# Sheet3.net
KiCad netlist of a schematic drawn in Altium Designer
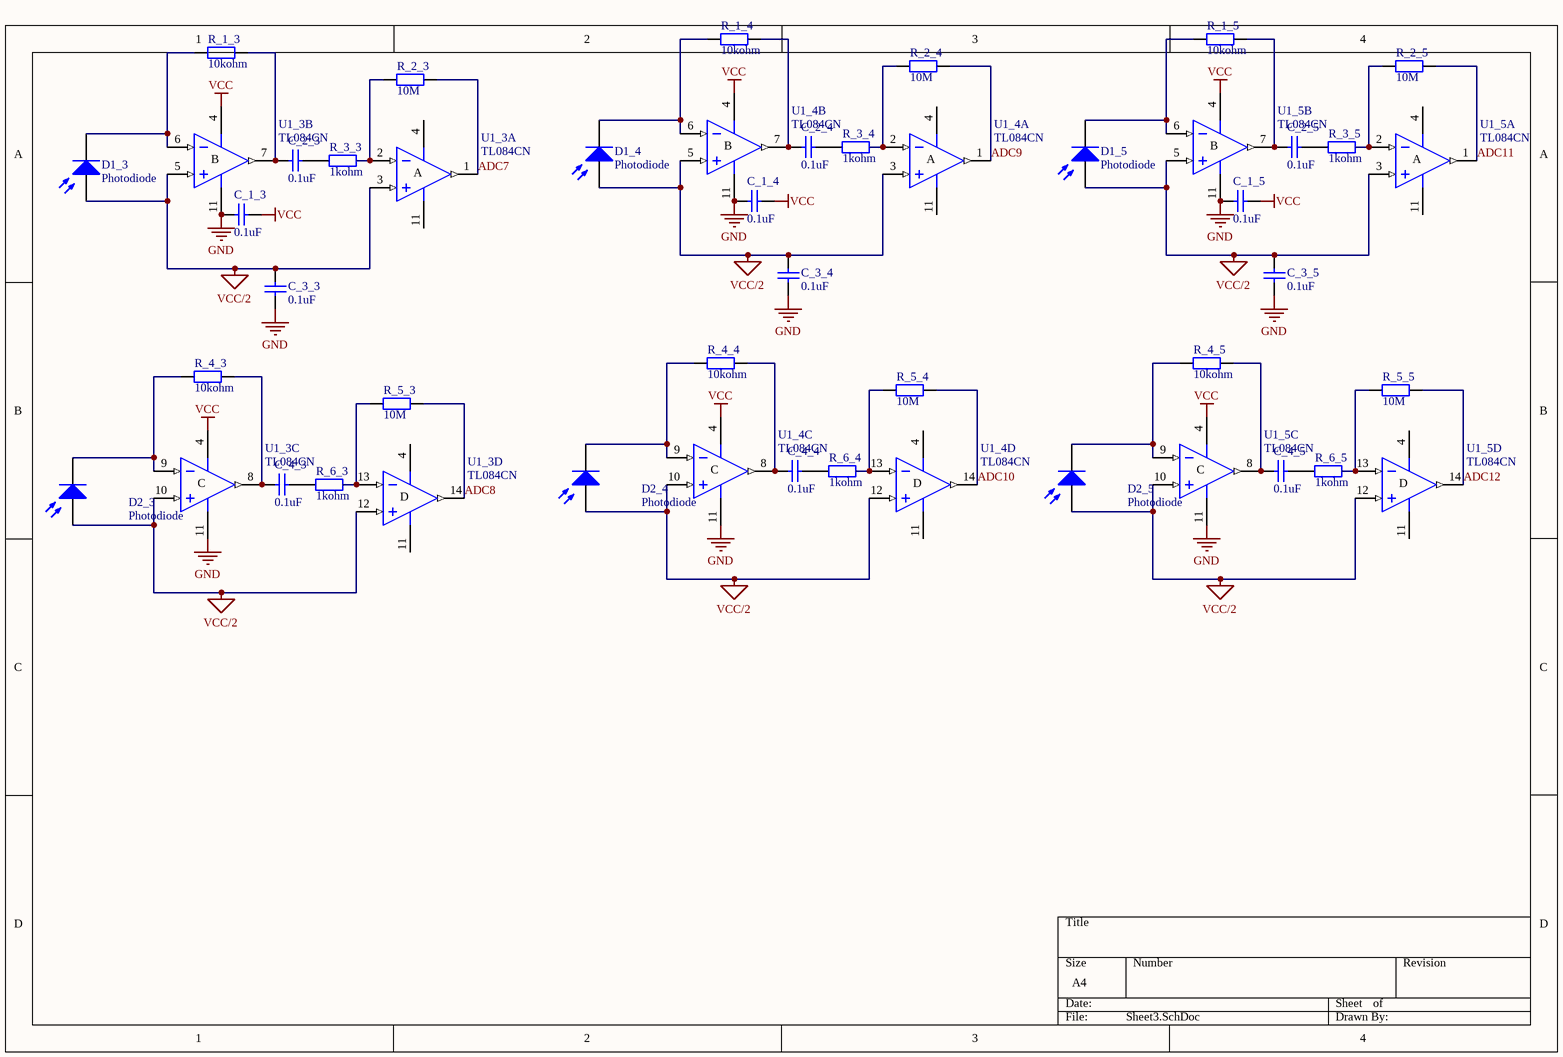
[diagram p0: Sheet3.SchDoc]

(export (version "E")
  (design (tool "Eeschema 10.0.6"))
  (components
    (comp (ref "C_1_3")
      (value "0.1uF")
      (footprint "cms805 - mini")
      (libsource (lib "lib_Robotronik") (part "Capa"))
    )
    (comp (ref "C_1_4")
      (value "0.1uF")
      (footprint "cms805 - mini")
      (libsource (lib "lib_Robotronik") (part "Capa"))
    )
    (comp (ref "C_1_5")
      (value "0.1uF")
      (footprint "cms805 - mini")
      (libsource (lib "lib_Robotronik") (part "Capa"))
    )
    (comp (ref "C_2_3")
      (value "0.1uF")
      (footprint "cms805 - mini")
      (libsource (lib "lib_Robotronik") (part "Capa"))
    )
    (comp (ref "C_2_4")
      (value "0.1uF")
      (footprint "cms805 - mini")
      (libsource (lib "lib_Robotronik") (part "Capa"))
    )
    (comp (ref "C_2_5")
      (value "0.1uF")
      (footprint "cms805 - mini")
      (libsource (lib "lib_Robotronik") (part "Capa"))
    )
    (comp (ref "C_3_3")
      (value "0.1uF")
      (footprint "cms805 - mini")
      (libsource (lib "lib_Robotronik") (part "Capa"))
    )
    (comp (ref "C_3_4")
      (value "0.1uF")
      (footprint "cms805 - mini")
      (libsource (lib "lib_Robotronik") (part "Capa"))
    )
    (comp (ref "C_3_5")
      (value "0.1uF")
      (footprint "cms805 - mini")
      (libsource (lib "lib_Robotronik") (part "Capa"))
    )
    (comp (ref "C_4_3")
      (value "0.1uF")
      (footprint "cms805 - mini")
      (libsource (lib "lib_Robotronik") (part "Capa"))
    )
    (comp (ref "C_4_4")
      (value "0.1uF")
      (footprint "cms805 - mini")
      (libsource (lib "lib_Robotronik") (part "Capa"))
    )
    (comp (ref "C_4_5")
      (value "0.1uF")
      (footprint "cms805 - mini")
      (libsource (lib "lib_Robotronik") (part "Capa"))
    )
    (comp (ref "D1_3")
      (value "Photodiode")
      (footprint "TEMD1000")
      (fields (field (name "PUBLISHER") "Altium Limited"))
      (libsource (lib "lib_Robotronik") (part "Photodiode"))
    )
    (comp (ref "D1_4")
      (value "Photodiode")
      (footprint "TEMD1000")
      (fields (field (name "PUBLISHER") "Altium Limited"))
      (libsource (lib "lib_Robotronik") (part "Photodiode"))
    )
    (comp (ref "D1_5")
      (value "Photodiode")
      (footprint "TEMD1000")
      (fields (field (name "PUBLISHER") "Altium Limited"))
      (libsource (lib "lib_Robotronik") (part "Photodiode"))
    )
    (comp (ref "D2_3")
      (value "Photodiode")
      (footprint "TEMD1000")
      (fields (field (name "PUBLISHER") "Altium Limited"))
      (libsource (lib "lib_Robotronik") (part "Photodiode"))
    )
    (comp (ref "D2_4")
      (value "Photodiode")
      (footprint "TEMD1000")
      (fields (field (name "PUBLISHER") "Altium Limited"))
      (libsource (lib "lib_Robotronik") (part "Photodiode"))
    )
    (comp (ref "D2_5")
      (value "Photodiode")
      (footprint "TEMD1000")
      (fields (field (name "PUBLISHER") "Altium Limited"))
      (libsource (lib "lib_Robotronik") (part "Photodiode"))
    )
    (comp (ref "R_1_3")
      (value "10kohm")
      (footprint "cms805 - mini")
      (libsource (lib "lib_Robotronik") (part "Resistance"))
    )
    (comp (ref "R_1_4")
      (value "10kohm")
      (footprint "cms805 - mini")
      (libsource (lib "lib_Robotronik") (part "Resistance"))
    )
    (comp (ref "R_1_5")
      (value "10kohm")
      (footprint "cms805 - mini")
      (libsource (lib "lib_Robotronik") (part "Resistance"))
    )
    (comp (ref "R_2_3")
      (value "10M")
      (footprint "cms805 - mini")
      (libsource (lib "lib_Robotronik") (part "Resistance"))
    )
    (comp (ref "R_2_4")
      (value "10M")
      (footprint "cms805 - mini")
      (libsource (lib "lib_Robotronik") (part "Resistance"))
    )
    (comp (ref "R_2_5")
      (value "10M")
      (footprint "cms805 - mini")
      (libsource (lib "lib_Robotronik") (part "Resistance"))
    )
    (comp (ref "R_3_3")
      (value "1kohm")
      (footprint "cms805 - mini")
      (libsource (lib "lib_Robotronik") (part "Resistance"))
    )
    (comp (ref "R_3_4")
      (value "1kohm")
      (footprint "cms805 - mini")
      (libsource (lib "lib_Robotronik") (part "Resistance"))
    )
    (comp (ref "R_3_5")
      (value "1kohm")
      (footprint "cms805 - mini")
      (libsource (lib "lib_Robotronik") (part "Resistance"))
    )
    (comp (ref "R_4_3")
      (value "10kohm")
      (footprint "cms805 - mini")
      (libsource (lib "lib_Robotronik") (part "Resistance"))
    )
    (comp (ref "R_4_4")
      (value "10kohm")
      (footprint "cms805 - mini")
      (libsource (lib "lib_Robotronik") (part "Resistance"))
    )
    (comp (ref "R_4_5")
      (value "10kohm")
      (footprint "cms805 - mini")
      (libsource (lib "lib_Robotronik") (part "Resistance"))
    )
    (comp (ref "R_5_3")
      (value "10M")
      (footprint "cms805 - mini")
      (libsource (lib "lib_Robotronik") (part "Resistance"))
    )
    (comp (ref "R_5_4")
      (value "10M")
      (footprint "cms805 - mini")
      (libsource (lib "lib_Robotronik") (part "Resistance"))
    )
    (comp (ref "R_5_5")
      (value "10M")
      (footprint "cms805 - mini")
      (libsource (lib "lib_Robotronik") (part "Resistance"))
    )
    (comp (ref "R_6_3")
      (value "1kohm")
      (footprint "cms805 - mini")
      (libsource (lib "lib_Robotronik") (part "Resistance"))
    )
    (comp (ref "R_6_4")
      (value "1kohm")
      (footprint "cms805 - mini")
      (libsource (lib "lib_Robotronik") (part "Resistance"))
    )
    (comp (ref "R_6_5")
      (value "1kohm")
      (footprint "cms805 - mini")
      (libsource (lib "lib_Robotronik") (part "Resistance"))
    )
    (comp (ref "U1_3")
      (value "TL084CN")
      (footprint "TSSOP14")
      (description "General-Purpose J-FET Quad Operational Amplifier")
      (fields (field (name "PUBLISHER") "Altium Limited"))
      (libsource (lib "lib_Robotronik") (part "TL084CN"))
    )
    (comp (ref "U1_4")
      (value "TL084CN")
      (footprint "TSSOP14")
      (description "General-Purpose J-FET Quad Operational Amplifier")
      (fields (field (name "PUBLISHER") "Altium Limited"))
      (libsource (lib "lib_Robotronik") (part "TL084CN"))
    )
    (comp (ref "U1_5")
      (value "TL084CN")
      (footprint "TSSOP14")
      (description "General-Purpose J-FET Quad Operational Amplifier")
      (fields (field (name "PUBLISHER") "Altium Limited"))
      (libsource (lib "lib_Robotronik") (part "TL084CN"))
    )
  )
  (nets
    (net (code "1") (name "/ADC7") (class "Default")
      (node (ref "R_2_3") (pin "2") (pinfunction "2_2") (pintype "passive"))
      (node (ref "U1_3") (pin "1") (pinfunction "OUT_1") (pintype "output"))
    )
    (net (code "2") (name "/ADC8") (class "Default")
      (node (ref "R_5_3") (pin "2") (pinfunction "2_2") (pintype "passive"))
      (node (ref "U1_3") (pin "14") (pinfunction "OUT_14") (pintype "output"))
    )
    (net (code "3") (name "/ADC9") (class "Default")
      (node (ref "R_2_4") (pin "2") (pinfunction "2_2") (pintype "passive"))
      (node (ref "U1_4") (pin "1") (pinfunction "OUT_1") (pintype "output"))
    )
    (net (code "4") (name "/ADC10") (class "Default")
      (node (ref "R_5_4") (pin "2") (pinfunction "2_2") (pintype "passive"))
      (node (ref "U1_4") (pin "14") (pinfunction "OUT_14") (pintype "output"))
    )
    (net (code "5") (name "/ADC11") (class "Default")
      (node (ref "R_2_5") (pin "2") (pinfunction "2_2") (pintype "passive"))
      (node (ref "U1_5") (pin "1") (pinfunction "OUT_1") (pintype "output"))
    )
    (net (code "6") (name "/ADC12") (class "Default")
      (node (ref "R_5_5") (pin "2") (pinfunction "2_2") (pintype "passive"))
      (node (ref "U1_5") (pin "14") (pinfunction "OUT_14") (pintype "output"))
    )
    (net (code "7") (name "GND") (class "Default")
      (node (ref "C_1_3") (pin "1") (pinfunction "1_1") (pintype "passive"))
      (node (ref "C_1_4") (pin "1") (pinfunction "1_1") (pintype "passive"))
      (node (ref "C_1_5") (pin "1") (pinfunction "1_1") (pintype "passive"))
      (node (ref "C_3_3") (pin "1") (pinfunction "1_1") (pintype "passive"))
      (node (ref "C_3_4") (pin "1") (pinfunction "1_1") (pintype "passive"))
      (node (ref "C_3_5") (pin "1") (pinfunction "1_1") (pintype "passive"))
      (node (ref "U1_3") (pin "11") (pinfunction "V-_11") (pintype "power_in"))
      (node (ref "U1_4") (pin "11") (pinfunction "V-_11") (pintype "power_in"))
      (node (ref "U1_5") (pin "11") (pinfunction "V-_11") (pintype "power_in"))
    )
    (net (code "8") (name "Net-(C_2_3-Pad1)") (class "Default")
      (node (ref "C_2_3") (pin "1") (pinfunction "1_1") (pintype "passive"))
      (node (ref "R_3_3") (pin "1") (pinfunction "1_1") (pintype "passive"))
    )
    (net (code "9") (name "Net-(C_2_4-Pad1)") (class "Default")
      (node (ref "C_2_4") (pin "1") (pinfunction "1_1") (pintype "passive"))
      (node (ref "R_3_4") (pin "1") (pinfunction "1_1") (pintype "passive"))
    )
    (net (code "10") (name "Net-(C_2_5-Pad1)") (class "Default")
      (node (ref "C_2_5") (pin "1") (pinfunction "1_1") (pintype "passive"))
      (node (ref "R_3_5") (pin "1") (pinfunction "1_1") (pintype "passive"))
    )
    (net (code "11") (name "Net-(C_4_3-Pad1)") (class "Default")
      (node (ref "C_4_3") (pin "1") (pinfunction "1_1") (pintype "passive"))
      (node (ref "R_6_3") (pin "1") (pinfunction "1_1") (pintype "passive"))
    )
    (net (code "12") (name "Net-(C_4_4-Pad1)") (class "Default")
      (node (ref "C_4_4") (pin "1") (pinfunction "1_1") (pintype "passive"))
      (node (ref "R_6_4") (pin "1") (pinfunction "1_1") (pintype "passive"))
    )
    (net (code "13") (name "Net-(C_4_5-Pad1)") (class "Default")
      (node (ref "C_4_5") (pin "1") (pinfunction "1_1") (pintype "passive"))
      (node (ref "R_6_5") (pin "1") (pinfunction "1_1") (pintype "passive"))
    )
    (net (code "14") (name "Net-(D1_3-K)") (class "Default")
      (node (ref "D1_3") (pin "2") (pinfunction "K_2") (pintype "passive"))
      (node (ref "R_1_3") (pin "1") (pinfunction "1_1") (pintype "passive"))
      (node (ref "U1_3") (pin "6") (pinfunction "IN-_6") (pintype "input"))
    )
    (net (code "15") (name "Net-(D1_4-K)") (class "Default")
      (node (ref "D1_4") (pin "2") (pinfunction "K_2") (pintype "passive"))
      (node (ref "R_1_4") (pin "1") (pinfunction "1_1") (pintype "passive"))
      (node (ref "U1_4") (pin "6") (pinfunction "IN-_6") (pintype "input"))
    )
    (net (code "16") (name "Net-(D1_5-K)") (class "Default")
      (node (ref "D1_5") (pin "2") (pinfunction "K_2") (pintype "passive"))
      (node (ref "R_1_5") (pin "1") (pinfunction "1_1") (pintype "passive"))
      (node (ref "U1_5") (pin "6") (pinfunction "IN-_6") (pintype "input"))
    )
    (net (code "17") (name "Net-(D2_3-K)") (class "Default")
      (node (ref "D2_3") (pin "2") (pinfunction "K_2") (pintype "passive"))
      (node (ref "R_4_3") (pin "1") (pinfunction "1_1") (pintype "passive"))
      (node (ref "U1_3") (pin "9") (pinfunction "IN-_9") (pintype "input"))
    )
    (net (code "18") (name "Net-(D2_4-K)") (class "Default")
      (node (ref "D2_4") (pin "2") (pinfunction "K_2") (pintype "passive"))
      (node (ref "R_4_4") (pin "1") (pinfunction "1_1") (pintype "passive"))
      (node (ref "U1_4") (pin "9") (pinfunction "IN-_9") (pintype "input"))
    )
    (net (code "19") (name "Net-(D2_5-K)") (class "Default")
      (node (ref "D2_5") (pin "2") (pinfunction "K_2") (pintype "passive"))
      (node (ref "R_4_5") (pin "1") (pinfunction "1_1") (pintype "passive"))
      (node (ref "U1_5") (pin "9") (pinfunction "IN-_9") (pintype "input"))
    )
    (net (code "20") (name "Net-(U1_3A-IN-)") (class "Default")
      (node (ref "R_2_3") (pin "1") (pinfunction "1_1") (pintype "passive"))
      (node (ref "R_3_3") (pin "2") (pinfunction "2_2") (pintype "passive"))
      (node (ref "U1_3") (pin "2") (pinfunction "IN-_2") (pintype "input"))
    )
    (net (code "21") (name "Net-(U1_3B-OUT)") (class "Default")
      (node (ref "C_2_3") (pin "2") (pinfunction "2_2") (pintype "passive"))
      (node (ref "R_1_3") (pin "2") (pinfunction "2_2") (pintype "passive"))
      (node (ref "U1_3") (pin "7") (pinfunction "OUT_7") (pintype "output"))
    )
    (net (code "22") (name "Net-(U1_3C-OUT)") (class "Default")
      (node (ref "C_4_3") (pin "2") (pinfunction "2_2") (pintype "passive"))
      (node (ref "R_4_3") (pin "2") (pinfunction "2_2") (pintype "passive"))
      (node (ref "U1_3") (pin "8") (pinfunction "OUT_8") (pintype "output"))
    )
    (net (code "23") (name "Net-(U1_3D-IN-)") (class "Default")
      (node (ref "R_5_3") (pin "1") (pinfunction "1_1") (pintype "passive"))
      (node (ref "R_6_3") (pin "2") (pinfunction "2_2") (pintype "passive"))
      (node (ref "U1_3") (pin "13") (pinfunction "IN-_13") (pintype "input"))
    )
    (net (code "24") (name "Net-(U1_4A-IN-)") (class "Default")
      (node (ref "R_2_4") (pin "1") (pinfunction "1_1") (pintype "passive"))
      (node (ref "R_3_4") (pin "2") (pinfunction "2_2") (pintype "passive"))
      (node (ref "U1_4") (pin "2") (pinfunction "IN-_2") (pintype "input"))
    )
    (net (code "25") (name "Net-(U1_4B-OUT)") (class "Default")
      (node (ref "C_2_4") (pin "2") (pinfunction "2_2") (pintype "passive"))
      (node (ref "R_1_4") (pin "2") (pinfunction "2_2") (pintype "passive"))
      (node (ref "U1_4") (pin "7") (pinfunction "OUT_7") (pintype "output"))
    )
    (net (code "26") (name "Net-(U1_4C-OUT)") (class "Default")
      (node (ref "C_4_4") (pin "2") (pinfunction "2_2") (pintype "passive"))
      (node (ref "R_4_4") (pin "2") (pinfunction "2_2") (pintype "passive"))
      (node (ref "U1_4") (pin "8") (pinfunction "OUT_8") (pintype "output"))
    )
    (net (code "27") (name "Net-(U1_4D-IN-)") (class "Default")
      (node (ref "R_5_4") (pin "1") (pinfunction "1_1") (pintype "passive"))
      (node (ref "R_6_4") (pin "2") (pinfunction "2_2") (pintype "passive"))
      (node (ref "U1_4") (pin "13") (pinfunction "IN-_13") (pintype "input"))
    )
    (net (code "28") (name "Net-(U1_5A-IN-)") (class "Default")
      (node (ref "R_2_5") (pin "1") (pinfunction "1_1") (pintype "passive"))
      (node (ref "R_3_5") (pin "2") (pinfunction "2_2") (pintype "passive"))
      (node (ref "U1_5") (pin "2") (pinfunction "IN-_2") (pintype "input"))
    )
    (net (code "29") (name "Net-(U1_5B-OUT)") (class "Default")
      (node (ref "C_2_5") (pin "2") (pinfunction "2_2") (pintype "passive"))
      (node (ref "R_1_5") (pin "2") (pinfunction "2_2") (pintype "passive"))
      (node (ref "U1_5") (pin "7") (pinfunction "OUT_7") (pintype "output"))
    )
    (net (code "30") (name "Net-(U1_5C-OUT)") (class "Default")
      (node (ref "C_4_5") (pin "2") (pinfunction "2_2") (pintype "passive"))
      (node (ref "R_4_5") (pin "2") (pinfunction "2_2") (pintype "passive"))
      (node (ref "U1_5") (pin "8") (pinfunction "OUT_8") (pintype "output"))
    )
    (net (code "31") (name "Net-(U1_5D-IN-)") (class "Default")
      (node (ref "R_5_5") (pin "1") (pinfunction "1_1") (pintype "passive"))
      (node (ref "R_6_5") (pin "2") (pinfunction "2_2") (pintype "passive"))
      (node (ref "U1_5") (pin "13") (pinfunction "IN-_13") (pintype "input"))
    )
    (net (code "32") (name "VCC") (class "Default")
      (node (ref "C_1_3") (pin "2") (pinfunction "2_2") (pintype "passive"))
      (node (ref "C_1_4") (pin "2") (pinfunction "2_2") (pintype "passive"))
      (node (ref "C_1_5") (pin "2") (pinfunction "2_2") (pintype "passive"))
      (node (ref "U1_3") (pin "4") (pinfunction "V+_4") (pintype "power_in"))
      (node (ref "U1_4") (pin "4") (pinfunction "V+_4") (pintype "power_in"))
      (node (ref "U1_5") (pin "4") (pinfunction "V+_4") (pintype "power_in"))
    )
    (net (code "33") (name "VCC{slash}2") (class "Default")
      (node (ref "C_3_3") (pin "2") (pinfunction "2_2") (pintype "passive"))
      (node (ref "C_3_4") (pin "2") (pinfunction "2_2") (pintype "passive"))
      (node (ref "C_3_5") (pin "2") (pinfunction "2_2") (pintype "passive"))
      (node (ref "D1_3") (pin "1") (pinfunction "A_1") (pintype "passive"))
      (node (ref "D1_4") (pin "1") (pinfunction "A_1") (pintype "passive"))
      (node (ref "D1_5") (pin "1") (pinfunction "A_1") (pintype "passive"))
      (node (ref "D2_3") (pin "1") (pinfunction "A_1") (pintype "passive"))
      (node (ref "D2_4") (pin "1") (pinfunction "A_1") (pintype "passive"))
      (node (ref "D2_5") (pin "1") (pinfunction "A_1") (pintype "passive"))
      (node (ref "U1_3") (pin "10") (pinfunction "IN+_10") (pintype "input"))
      (node (ref "U1_3") (pin "12") (pinfunction "IN+_12") (pintype "input"))
      (node (ref "U1_3") (pin "3") (pinfunction "IN+_3") (pintype "input"))
      (node (ref "U1_3") (pin "5") (pinfunction "IN+_5") (pintype "input"))
      (node (ref "U1_4") (pin "10") (pinfunction "IN+_10") (pintype "input"))
      (node (ref "U1_4") (pin "12") (pinfunction "IN+_12") (pintype "input"))
      (node (ref "U1_4") (pin "3") (pinfunction "IN+_3") (pintype "input"))
      (node (ref "U1_4") (pin "5") (pinfunction "IN+_5") (pintype "input"))
      (node (ref "U1_5") (pin "10") (pinfunction "IN+_10") (pintype "input"))
      (node (ref "U1_5") (pin "12") (pinfunction "IN+_12") (pintype "input"))
      (node (ref "U1_5") (pin "3") (pinfunction "IN+_3") (pintype "input"))
      (node (ref "U1_5") (pin "5") (pinfunction "IN+_5") (pintype "input"))
    )
    (net (code "34") (name "unconnected-(U1_3A-V+-Pad4)") (class "Default")
      (node (ref "U1_3") (pin "4") (pinfunction "V+_4") (pintype "power_in"))
    )
    (net (code "35") (name "unconnected-(U1_3A-V--Pad11)") (class "Default")
      (node (ref "U1_3") (pin "11") (pinfunction "V-_11") (pintype "power_in"))
    )
    (net (code "36") (name "unconnected-(U1_3D-V+-Pad4)") (class "Default")
      (node (ref "U1_3") (pin "4") (pinfunction "V+_4") (pintype "power_in"))
    )
    (net (code "37") (name "unconnected-(U1_3D-V--Pad11)") (class "Default")
      (node (ref "U1_3") (pin "11") (pinfunction "V-_11") (pintype "power_in"))
    )
    (net (code "38") (name "unconnected-(U1_4A-V+-Pad4)") (class "Default")
      (node (ref "U1_4") (pin "4") (pinfunction "V+_4") (pintype "power_in"))
    )
    (net (code "39") (name "unconnected-(U1_4A-V--Pad11)") (class "Default")
      (node (ref "U1_4") (pin "11") (pinfunction "V-_11") (pintype "power_in"))
    )
    (net (code "40") (name "unconnected-(U1_4D-V+-Pad4)") (class "Default")
      (node (ref "U1_4") (pin "4") (pinfunction "V+_4") (pintype "power_in"))
    )
    (net (code "41") (name "unconnected-(U1_4D-V--Pad11)") (class "Default")
      (node (ref "U1_4") (pin "11") (pinfunction "V-_11") (pintype "power_in"))
    )
    (net (code "42") (name "unconnected-(U1_5A-V+-Pad4)") (class "Default")
      (node (ref "U1_5") (pin "4") (pinfunction "V+_4") (pintype "power_in"))
    )
    (net (code "43") (name "unconnected-(U1_5A-V--Pad11)") (class "Default")
      (node (ref "U1_5") (pin "11") (pinfunction "V-_11") (pintype "power_in"))
    )
    (net (code "44") (name "unconnected-(U1_5D-V+-Pad4)") (class "Default")
      (node (ref "U1_5") (pin "4") (pinfunction "V+_4") (pintype "power_in"))
    )
    (net (code "45") (name "unconnected-(U1_5D-V--Pad11)") (class "Default")
      (node (ref "U1_5") (pin "11") (pinfunction "V-_11") (pintype "power_in"))
    )
  )
)
